# MCU_2.net
KiCad netlist of a schematic drawn in Altium Designer
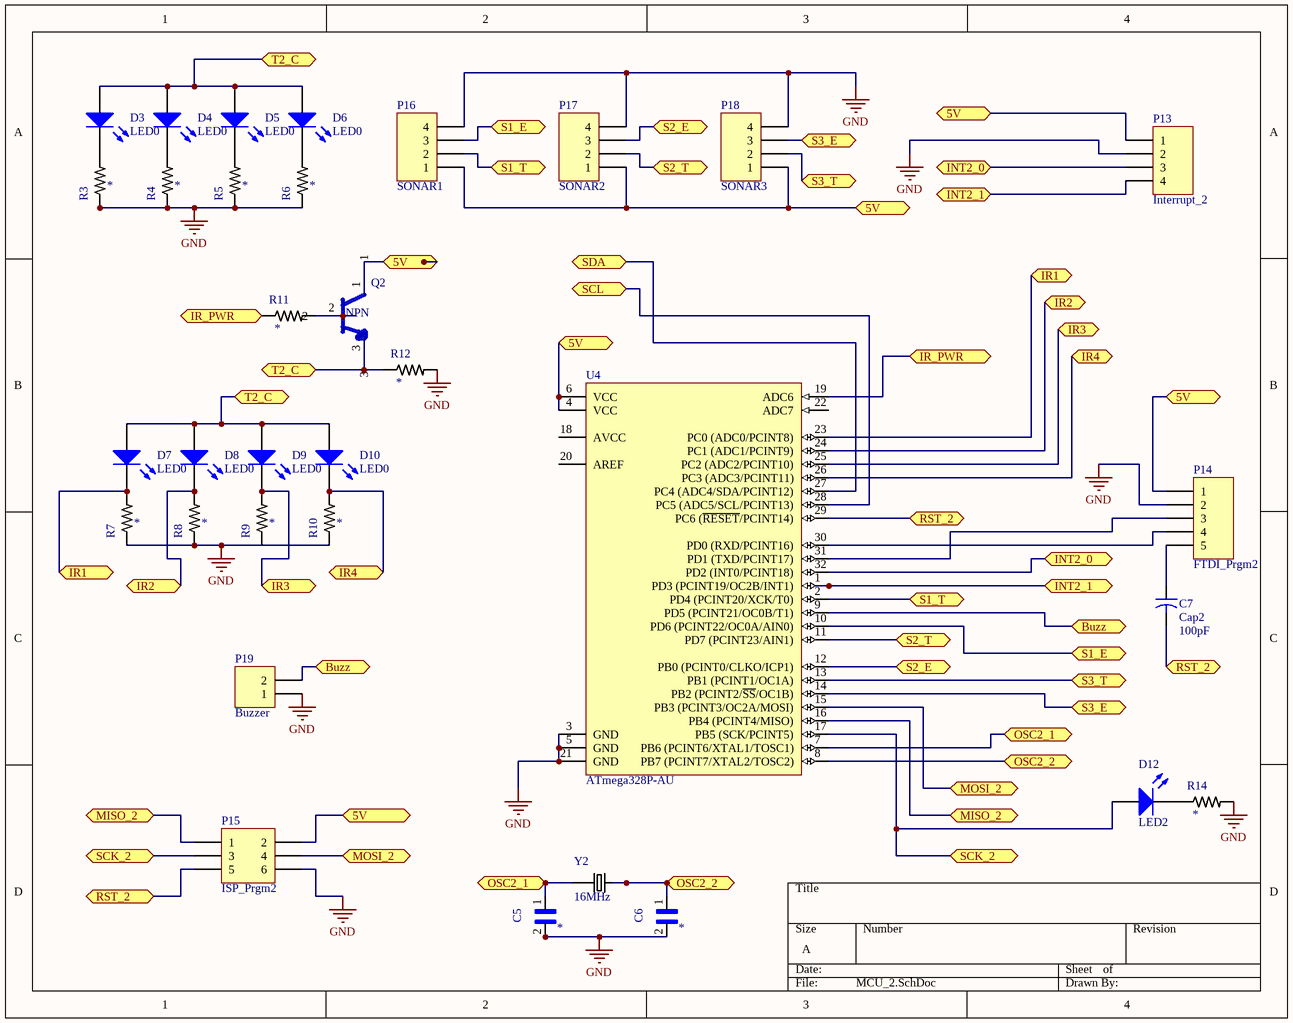
[diagram p0: MCU_2.SchDoc]

(export (version "E")
  (design (tool "Eeschema 10.0.6"))
  (components
    (comp (ref "C5")
      (value "Cap_0805")
      (footprint "CAP_0805")
      (description "Cap Ceramic 10uF 10V X5R 10% SMD 0805 85Â°C Embossed Plastic T/R")
      (fields
        (field (name "MF") "Samsung Electro-Mechanics")
        (field (name "MP") "CL21A106KPFNNWE")
        (field (name "ALTIUM_VALUE") "*")
      )
      (libsource (lib "IResc_lib") (part "Cap_0805"))
    )
    (comp (ref "C6")
      (value "Cap_0805")
      (footprint "CAP_0805")
      (description "Cap Ceramic 10uF 10V X5R 10% SMD 0805 85Â°C Embossed Plastic T/R")
      (fields
        (field (name "MF") "Samsung Electro-Mechanics")
        (field (name "MP") "CL21A106KPFNNWE")
        (field (name "ALTIUM_VALUE") "*")
      )
      (libsource (lib "IResc_lib") (part "Cap_0805"))
    )
    (comp (ref "C7")
      (value "Cap2")
      (footprint "CAPR5-4X5")
      (description "Capacitor")
      (fields (field (name "ALTIUM_VALUE") "100pF") (field (name "PUBLISHER") "Altium Limited"))
      (libsource (lib "Miscellaneous Devices") (part "Cap2"))
    )
    (comp (ref "D3")
      (value "LED0")
      (footprint "LED-1")
      (description "Typical INFRARED GaAs LED")
      (fields (field (name "PUBLISHER") "Altium Limited"))
      (libsource (lib "Miscellaneous Devices") (part "LED0"))
    )
    (comp (ref "D4")
      (value "LED0")
      (footprint "LED-1")
      (description "Typical INFRARED GaAs LED")
      (fields (field (name "PUBLISHER") "Altium Limited"))
      (libsource (lib "Miscellaneous Devices") (part "LED0"))
    )
    (comp (ref "D5")
      (value "LED0")
      (footprint "LED-1")
      (description "Typical INFRARED GaAs LED")
      (fields (field (name "PUBLISHER") "Altium Limited"))
      (libsource (lib "Miscellaneous Devices") (part "LED0"))
    )
    (comp (ref "D6")
      (value "LED0")
      (footprint "LED-1")
      (description "Typical INFRARED GaAs LED")
      (fields (field (name "PUBLISHER") "Altium Limited"))
      (libsource (lib "Miscellaneous Devices") (part "LED0"))
    )
    (comp (ref "D7")
      (value "LED0")
      (footprint "LED-1")
      (description "Typical INFRARED GaAs LED")
      (fields (field (name "PUBLISHER") "Altium Limited"))
      (libsource (lib "Miscellaneous Devices") (part "LED0"))
    )
    (comp (ref "D8")
      (value "LED0")
      (footprint "LED-1")
      (description "Typical INFRARED GaAs LED")
      (fields (field (name "PUBLISHER") "Altium Limited"))
      (libsource (lib "Miscellaneous Devices") (part "LED0"))
    )
    (comp (ref "D9")
      (value "LED0")
      (footprint "LED-1")
      (description "Typical INFRARED GaAs LED")
      (fields (field (name "PUBLISHER") "Altium Limited"))
      (libsource (lib "Miscellaneous Devices") (part "LED0"))
    )
    (comp (ref "D10")
      (value "LED0")
      (footprint "LED-1")
      (description "Typical INFRARED GaAs LED")
      (fields (field (name "PUBLISHER") "Altium Limited"))
      (libsource (lib "Miscellaneous Devices") (part "LED0"))
    )
    (comp (ref "D12")
      (value "LED2")
      (footprint "3.2X1.6X1.1")
      (description "Typical RED, GREEN, YELLOW, AMBER GaAs LED")
      (fields (field (name "PUBLISHER") "Altium Limited"))
      (libsource (lib "Miscellaneous Devices") (part "LED2"))
    )
    (comp (ref "P13")
      (value "Interrupt_2")
      (footprint "HDR1X4")
      (description "Header, 4-Pin")
      (fields (field (name "PUBLISHER") "Altium Limited"))
      (libsource (lib "") (part "Header 4_1"))
    )
    (comp (ref "P14")
      (value "FTDI_Prgm2")
      (footprint "HDR1X5")
      (description "Header, 5-Pin")
      (fields (field (name "PUBLISHER") "Altium Limited"))
      (libsource (lib "Miscellaneous Connectors") (part "Header 5"))
    )
    (comp (ref "P15")
      (value "ISP_Prgm2")
      (footprint "HDR2X3")
      (description "Header, 3-Pin, Dual row")
      (fields (field (name "PUBLISHER") "Altium Limited"))
      (libsource (lib "Miscellaneous Connectors") (part "Header 3X2"))
    )
    (comp (ref "P16")
      (value "SONAR1")
      (footprint "HDR1X4")
      (description "Header, 4-Pin")
      (fields (field (name "PUBLISHER") "Altium Limited"))
      (libsource (lib "Miscellaneous Connectors") (part "Header 4"))
    )
    (comp (ref "P17")
      (value "SONAR2")
      (footprint "HDR1X4")
      (description "Header, 4-Pin")
      (fields (field (name "PUBLISHER") "Altium Limited"))
      (libsource (lib "Miscellaneous Connectors") (part "Header 4"))
    )
    (comp (ref "P18")
      (value "SONAR3")
      (footprint "HDR1X4")
      (description "Header, 4-Pin")
      (fields (field (name "PUBLISHER") "Altium Limited"))
      (libsource (lib "Miscellaneous Connectors") (part "Header 4"))
    )
    (comp (ref "P19")
      (value "Buzzer")
      (footprint "HDR1X2")
      (description "Header, 2-Pin")
      (fields (field (name "PUBLISHER") "Altium Limited"))
      (libsource (lib "Miscellaneous Connectors") (part "Header 2"))
    )
    (comp (ref "Q2")
      (value "NPN")
      (footprint "NPN-d400")
      (description "NPN- d400")
      (libsource (lib "NPN-d400") (part "Component_1"))
    )
    (comp (ref "R3")
      (value "Res_0805")
      (footprint "Res_0805")
      (description "Res Thick Film 0805 392 Ohm 1% 1/3W Â±100ppm/Â°C Molded SMD SMD T/R")
      (fields
        (field (name "MP") "CRGH0805F392R")
        (field (name "MF") "TE Connectivity")
        (field (name "ALTIUM_VALUE") "*")
      )
      (libsource (lib "IResc_lib") (part "Res_0805"))
    )
    (comp (ref "R4")
      (value "Res_0805")
      (footprint "Res_0805")
      (description "Res Thick Film 0805 392 Ohm 1% 1/3W Â±100ppm/Â°C Molded SMD SMD T/R")
      (fields
        (field (name "MP") "CRGH0805F392R")
        (field (name "MF") "TE Connectivity")
        (field (name "ALTIUM_VALUE") "*")
      )
      (libsource (lib "IResc_lib") (part "Res_0805"))
    )
    (comp (ref "R5")
      (value "Res_0805")
      (footprint "Res_0805")
      (description "Res Thick Film 0805 392 Ohm 1% 1/3W Â±100ppm/Â°C Molded SMD SMD T/R")
      (fields
        (field (name "MP") "CRGH0805F392R")
        (field (name "MF") "TE Connectivity")
        (field (name "ALTIUM_VALUE") "*")
      )
      (libsource (lib "IResc_lib") (part "Res_0805"))
    )
    (comp (ref "R6")
      (value "Res_0805")
      (footprint "Res_0805")
      (description "Res Thick Film 0805 392 Ohm 1% 1/3W Â±100ppm/Â°C Molded SMD SMD T/R")
      (fields
        (field (name "MP") "CRGH0805F392R")
        (field (name "MF") "TE Connectivity")
        (field (name "ALTIUM_VALUE") "*")
      )
      (libsource (lib "IResc_lib") (part "Res_0805"))
    )
    (comp (ref "R7")
      (value "Res_0805")
      (footprint "Res_0805")
      (description "Res Thick Film 0805 392 Ohm 1% 1/3W Â±100ppm/Â°C Molded SMD SMD T/R")
      (fields
        (field (name "MP") "CRGH0805F392R")
        (field (name "MF") "TE Connectivity")
        (field (name "ALTIUM_VALUE") "*")
      )
      (libsource (lib "IResc_lib") (part "Res_0805"))
    )
    (comp (ref "R8")
      (value "Res_0805")
      (footprint "Res_0805")
      (description "Res Thick Film 0805 392 Ohm 1% 1/3W Â±100ppm/Â°C Molded SMD SMD T/R")
      (fields
        (field (name "MP") "CRGH0805F392R")
        (field (name "MF") "TE Connectivity")
        (field (name "ALTIUM_VALUE") "*")
      )
      (libsource (lib "IResc_lib") (part "Res_0805"))
    )
    (comp (ref "R9")
      (value "Res_0805")
      (footprint "Res_0805")
      (description "Res Thick Film 0805 392 Ohm 1% 1/3W Â±100ppm/Â°C Molded SMD SMD T/R")
      (fields
        (field (name "MP") "CRGH0805F392R")
        (field (name "MF") "TE Connectivity")
        (field (name "ALTIUM_VALUE") "*")
      )
      (libsource (lib "IResc_lib") (part "Res_0805"))
    )
    (comp (ref "R10")
      (value "Res_0805")
      (footprint "Res_0805")
      (description "Res Thick Film 0805 392 Ohm 1% 1/3W Â±100ppm/Â°C Molded SMD SMD T/R")
      (fields
        (field (name "MP") "CRGH0805F392R")
        (field (name "MF") "TE Connectivity")
        (field (name "ALTIUM_VALUE") "*")
      )
      (libsource (lib "IResc_lib") (part "Res_0805"))
    )
    (comp (ref "R11")
      (value "Res_0805")
      (footprint "Res_0805")
      (description "Res Thick Film 0805 392 Ohm 1% 1/3W Â±100ppm/Â°C Molded SMD SMD T/R")
      (fields
        (field (name "MP") "CRGH0805F392R")
        (field (name "MF") "TE Connectivity")
        (field (name "ALTIUM_VALUE") "*")
      )
      (libsource (lib "IResc_lib") (part "Res_0805"))
    )
    (comp (ref "R12")
      (value "Res_0805")
      (footprint "Res_0805")
      (description "Res Thick Film 0805 392 Ohm 1% 1/3W Â±100ppm/Â°C Molded SMD SMD T/R")
      (fields
        (field (name "MP") "CRGH0805F392R")
        (field (name "MF") "TE Connectivity")
        (field (name "ALTIUM_VALUE") "*")
      )
      (libsource (lib "IResc_lib") (part "Res_0805"))
    )
    (comp (ref "R14")
      (value "Res_0805")
      (footprint "Res_0805")
      (description "Res Thick Film 0805 392 Ohm 1% 1/3W Â±100ppm/Â°C Molded SMD SMD T/R")
      (fields
        (field (name "MP") "CRGH0805F392R")
        (field (name "MF") "TE Connectivity")
        (field (name "ALTIUM_VALUE") "*")
      )
      (libsource (lib "IResc_lib") (part "Res_0805"))
    )
    (comp (ref "U4")
      (value "ATmega328P-AU")
      (footprint "32A_N")
      (fields (field (name "PUBLISHER") "Altium Limited"))
      (libsource (lib "Atmel Microcontroller 8-Bit megaAVR") (part "ATmega328P-AU"))
    )
    (comp (ref "Y2")
      (value "16MHz")
      (footprint "XTAL_THT")
      (description "Crystal 3.93216MHz 17pF 2-Pin HC-49/U")
      (fields (field (name "MF") "ECS Inc.") (field (name "MP") "ECS-39-17-1X"))
      (libsource (lib "IResc_lib") (part "Xtal_THT"))
    )
  )
  (nets
    (net (code "1") (name "/5V") (class "Default")
      (node (ref "P13") (pin "1") (pinfunction "1_1") (pintype "passive"))
      (node (ref "P14") (pin "1") (pinfunction "1_1") (pintype "passive"))
      (node (ref "P15") (pin "2") (pinfunction "2_2") (pintype "passive"))
      (node (ref "P16") (pin "1") (pinfunction "1_1") (pintype "passive"))
      (node (ref "P17") (pin "1") (pinfunction "1_1") (pintype "passive"))
      (node (ref "P18") (pin "1") (pinfunction "1_1") (pintype "passive"))
      (node (ref "Q2") (pin "1") (pinfunction "1_1") (pintype "passive"))
      (node (ref "U4") (pin "4") (pinfunction "VCC_4") (pintype "power_in"))
      (node (ref "U4") (pin "6") (pinfunction "VCC_6") (pintype "power_in"))
    )
    (net (code "2") (name "/Buzz") (class "Default")
      (node (ref "P19") (pin "2") (pinfunction "2_2") (pintype "passive"))
      (node (ref "U4") (pin "9") (pinfunction "PD5_(PCINT21/OC0B/T1)_9") (pintype "bidirectional"))
    )
    (net (code "3") (name "/INT2_0") (class "Default")
      (node (ref "P13") (pin "3") (pinfunction "3_3") (pintype "passive"))
      (node (ref "U4") (pin "32") (pinfunction "PD2_(INT0/PCINT18)_32") (pintype "bidirectional"))
    )
    (net (code "4") (name "/INT2_1") (class "Default")
      (node (ref "P13") (pin "4") (pinfunction "4_4") (pintype "passive"))
      (node (ref "U4") (pin "1") (pinfunction "PD3_(PCINT19/OC2B/INT1)_1") (pintype "bidirectional"))
    )
    (net (code "5") (name "/IR1") (class "Default")
      (node (ref "D7") (pin "2") (pinfunction "K_2") (pintype "passive"))
      (node (ref "R7") (pin "2") (pinfunction "2_2") (pintype "passive"))
      (node (ref "U4") (pin "23") (pinfunction "PC0_(ADC0/PCINT8)_23") (pintype "bidirectional"))
    )
    (net (code "6") (name "/IR2") (class "Default")
      (node (ref "D8") (pin "2") (pinfunction "K_2") (pintype "passive"))
      (node (ref "R8") (pin "2") (pinfunction "2_2") (pintype "passive"))
      (node (ref "U4") (pin "24") (pinfunction "PC1_(ADC1/PCINT9)_24") (pintype "bidirectional"))
    )
    (net (code "7") (name "/IR3") (class "Default")
      (node (ref "D9") (pin "2") (pinfunction "K_2") (pintype "passive"))
      (node (ref "R9") (pin "2") (pinfunction "2_2") (pintype "passive"))
      (node (ref "U4") (pin "25") (pinfunction "PC2_(ADC2/PCINT10)_25") (pintype "bidirectional"))
    )
    (net (code "8") (name "/IR4") (class "Default")
      (node (ref "D10") (pin "2") (pinfunction "K_2") (pintype "passive"))
      (node (ref "R10") (pin "2") (pinfunction "2_2") (pintype "passive"))
      (node (ref "U4") (pin "26") (pinfunction "PC3_(ADC3/PCINT11)_26") (pintype "bidirectional"))
    )
    (net (code "9") (name "/IR_PWR") (class "Default")
      (node (ref "R11") (pin "1") (pinfunction "1_1") (pintype "passive"))
      (node (ref "U4") (pin "19") (pinfunction "ADC6_19") (pintype "input"))
    )
    (net (code "10") (name "/MISO_2") (class "Default")
      (node (ref "P15") (pin "1") (pinfunction "1_1") (pintype "passive"))
      (node (ref "U4") (pin "16") (pinfunction "PB4_(PCINT4/MISO)_16") (pintype "bidirectional"))
    )
    (net (code "11") (name "/MOSI_2") (class "Default")
      (node (ref "P15") (pin "4") (pinfunction "4_4") (pintype "passive"))
      (node (ref "U4") (pin "15") (pinfunction "PB3_(PCINT3/OC2A/MOSI)_15") (pintype "bidirectional"))
    )
    (net (code "12") (name "/OSC2_1") (class "Default")
      (node (ref "C5") (pin "1") (pinfunction "1_1") (pintype "passive"))
      (node (ref "U4") (pin "7") (pinfunction "PB6_(PCINT6/XTAL1/TOSC1)_7") (pintype "bidirectional"))
      (node (ref "Y2") (pin "1") (pinfunction "1_1") (pintype "passive"))
    )
    (net (code "13") (name "/OSC2_2") (class "Default")
      (node (ref "C6") (pin "1") (pinfunction "1_1") (pintype "passive"))
      (node (ref "U4") (pin "8") (pinfunction "PB7_(PCINT7/XTAL2/TOSC2)_8") (pintype "bidirectional"))
      (node (ref "Y2") (pin "2") (pinfunction "2_2") (pintype "passive"))
    )
    (net (code "14") (name "/RST_2") (class "Default")
      (node (ref "C7") (pin "2") (pinfunction "2_2") (pintype "passive"))
      (node (ref "P15") (pin "5") (pinfunction "5_5") (pintype "passive"))
      (node (ref "U4") (pin "29") (pinfunction "PC6_(~{RESET}/PCINT14)_29") (pintype "bidirectional"))
    )
    (net (code "15") (name "/S1_E") (class "Default")
      (node (ref "P16") (pin "3") (pinfunction "3_3") (pintype "passive"))
      (node (ref "U4") (pin "10") (pinfunction "PD6_(PCINT22/OC0A/AIN0)_10") (pintype "bidirectional"))
    )
    (net (code "16") (name "/S1_T") (class "Default")
      (node (ref "P16") (pin "2") (pinfunction "2_2") (pintype "passive"))
      (node (ref "U4") (pin "2") (pinfunction "PD4_(PCINT20/XCK/T0)_2") (pintype "bidirectional"))
    )
    (net (code "17") (name "/S2_E") (class "Default")
      (node (ref "P17") (pin "3") (pinfunction "3_3") (pintype "passive"))
      (node (ref "U4") (pin "12") (pinfunction "PB0_(PCINT0/CLKO/ICP1)_12") (pintype "bidirectional"))
    )
    (net (code "18") (name "/S2_T") (class "Default")
      (node (ref "P17") (pin "2") (pinfunction "2_2") (pintype "passive"))
      (node (ref "U4") (pin "11") (pinfunction "PD7_(PCINT23/AIN1)_11") (pintype "bidirectional"))
    )
    (net (code "19") (name "/S3_E") (class "Default")
      (node (ref "P18") (pin "3") (pinfunction "3_3") (pintype "passive"))
      (node (ref "U4") (pin "14") (pinfunction "PB2_(PCINT2/~{SS}/OC1B)_14") (pintype "bidirectional"))
    )
    (net (code "20") (name "/S3_T") (class "Default")
      (node (ref "P18") (pin "2") (pinfunction "2_2") (pintype "passive"))
      (node (ref "U4") (pin "13") (pinfunction "PB1_(PCINT1/OC1A)_13") (pintype "bidirectional"))
    )
    (net (code "21") (name "/SCK_2") (class "Default")
      (node (ref "D12") (pin "1") (pinfunction "A_1") (pintype "passive"))
      (node (ref "P15") (pin "3") (pinfunction "3_3") (pintype "passive"))
      (node (ref "U4") (pin "17") (pinfunction "PB5_(SCK/PCINT5)_17") (pintype "bidirectional"))
    )
    (net (code "22") (name "/SCL") (class "Default")
      (node (ref "U4") (pin "28") (pinfunction "PC5_(ADC5/SCL/PCINT13)_28") (pintype "bidirectional"))
    )
    (net (code "23") (name "/SDA") (class "Default")
      (node (ref "U4") (pin "27") (pinfunction "PC4_(ADC4/SDA/PCINT12)_27") (pintype "bidirectional"))
    )
    (net (code "24") (name "/T2_C") (class "Default")
      (node (ref "D10") (pin "1") (pinfunction "A_1") (pintype "passive"))
      (node (ref "D3") (pin "1") (pinfunction "A_1") (pintype "passive"))
      (node (ref "D4") (pin "1") (pinfunction "A_1") (pintype "passive"))
      (node (ref "D5") (pin "1") (pinfunction "A_1") (pintype "passive"))
      (node (ref "D6") (pin "1") (pinfunction "A_1") (pintype "passive"))
      (node (ref "D7") (pin "1") (pinfunction "A_1") (pintype "passive"))
      (node (ref "D8") (pin "1") (pinfunction "A_1") (pintype "passive"))
      (node (ref "D9") (pin "1") (pinfunction "A_1") (pintype "passive"))
      (node (ref "Q2") (pin "3") (pinfunction "3_3") (pintype "passive"))
      (node (ref "R12") (pin "1") (pinfunction "1_1") (pintype "passive"))
    )
    (net (code "25") (name "GND") (class "Default")
      (node (ref "C5") (pin "2") (pinfunction "2_2") (pintype "passive"))
      (node (ref "C6") (pin "2") (pinfunction "2_2") (pintype "passive"))
      (node (ref "P13") (pin "2") (pinfunction "2_2") (pintype "passive"))
      (node (ref "P14") (pin "2") (pinfunction "2_2") (pintype "passive"))
      (node (ref "P15") (pin "6") (pinfunction "6_6") (pintype "passive"))
      (node (ref "P16") (pin "4") (pinfunction "4_4") (pintype "passive"))
      (node (ref "P17") (pin "4") (pinfunction "4_4") (pintype "passive"))
      (node (ref "P18") (pin "4") (pinfunction "4_4") (pintype "passive"))
      (node (ref "P19") (pin "1") (pinfunction "1_1") (pintype "passive"))
      (node (ref "R10") (pin "1") (pinfunction "1_1") (pintype "passive"))
      (node (ref "R12") (pin "2") (pinfunction "2_2") (pintype "passive"))
      (node (ref "R14") (pin "2") (pinfunction "2_2") (pintype "passive"))
      (node (ref "R3") (pin "1") (pinfunction "1_1") (pintype "passive"))
      (node (ref "R4") (pin "1") (pinfunction "1_1") (pintype "passive"))
      (node (ref "R5") (pin "1") (pinfunction "1_1") (pintype "passive"))
      (node (ref "R6") (pin "1") (pinfunction "1_1") (pintype "passive"))
      (node (ref "R7") (pin "1") (pinfunction "1_1") (pintype "passive"))
      (node (ref "R8") (pin "1") (pinfunction "1_1") (pintype "passive"))
      (node (ref "R9") (pin "1") (pinfunction "1_1") (pintype "passive"))
      (node (ref "U4") (pin "21") (pinfunction "GND_21") (pintype "power_in"))
      (node (ref "U4") (pin "3") (pinfunction "GND_3") (pintype "power_in"))
      (node (ref "U4") (pin "5") (pinfunction "GND_5") (pintype "power_in"))
    )
    (net (code "26") (name "Net-(C7-Pad1)") (class "Default")
      (node (ref "C7") (pin "1") (pinfunction "1_1") (pintype "passive"))
      (node (ref "P14") (pin "5") (pinfunction "5_5") (pintype "passive"))
    )
    (net (code "27") (name "Net-(D3-K)") (class "Default")
      (node (ref "D3") (pin "2") (pinfunction "K_2") (pintype "passive"))
      (node (ref "R3") (pin "2") (pinfunction "2_2") (pintype "passive"))
    )
    (net (code "28") (name "Net-(D4-K)") (class "Default")
      (node (ref "D4") (pin "2") (pinfunction "K_2") (pintype "passive"))
      (node (ref "R4") (pin "2") (pinfunction "2_2") (pintype "passive"))
    )
    (net (code "29") (name "Net-(D5-K)") (class "Default")
      (node (ref "D5") (pin "2") (pinfunction "K_2") (pintype "passive"))
      (node (ref "R5") (pin "2") (pinfunction "2_2") (pintype "passive"))
    )
    (net (code "30") (name "Net-(D6-K)") (class "Default")
      (node (ref "D6") (pin "2") (pinfunction "K_2") (pintype "passive"))
      (node (ref "R6") (pin "2") (pinfunction "2_2") (pintype "passive"))
    )
    (net (code "31") (name "Net-(D12-K)") (class "Default")
      (node (ref "D12") (pin "2") (pinfunction "K_2") (pintype "passive"))
      (node (ref "R14") (pin "1") (pinfunction "1_1") (pintype "passive"))
    )
    (net (code "32") (name "Net-(Q2-Pad2)") (class "Default")
      (node (ref "Q2") (pin "2") (pinfunction "2_2") (pintype "passive"))
      (node (ref "R11") (pin "2") (pinfunction "2_2") (pintype "passive"))
    )
    (net (code "33") (name "Net-(U4-PD0_(RXD{slash}PCINT16))") (class "Default")
      (node (ref "P14") (pin "4") (pinfunction "4_4") (pintype "passive"))
      (node (ref "U4") (pin "30") (pinfunction "PD0_(RXD/PCINT16)_30") (pintype "bidirectional"))
    )
    (net (code "34") (name "Net-(U4-PD1_(TXD{slash}PCINT17))") (class "Default")
      (node (ref "P14") (pin "3") (pinfunction "3_3") (pintype "passive"))
      (node (ref "U4") (pin "31") (pinfunction "PD1_(TXD/PCINT17)_31") (pintype "bidirectional"))
    )
    (net (code "35") (name "unconnected-(U4-ADC7-Pad22)") (class "Default")
      (node (ref "U4") (pin "22") (pinfunction "ADC7_22") (pintype "input"))
    )
    (net (code "36") (name "unconnected-(U4-AREF-Pad20)") (class "Default")
      (node (ref "U4") (pin "20") (pinfunction "AREF_20") (pintype "passive"))
    )
    (net (code "37") (name "unconnected-(U4-AVCC-Pad18)") (class "Default")
      (node (ref "U4") (pin "18") (pinfunction "AVCC_18") (pintype "power_in"))
    )
  )
)
